# nfc_lock.net
KiCad netlist of a schematic drawn in EAGLE
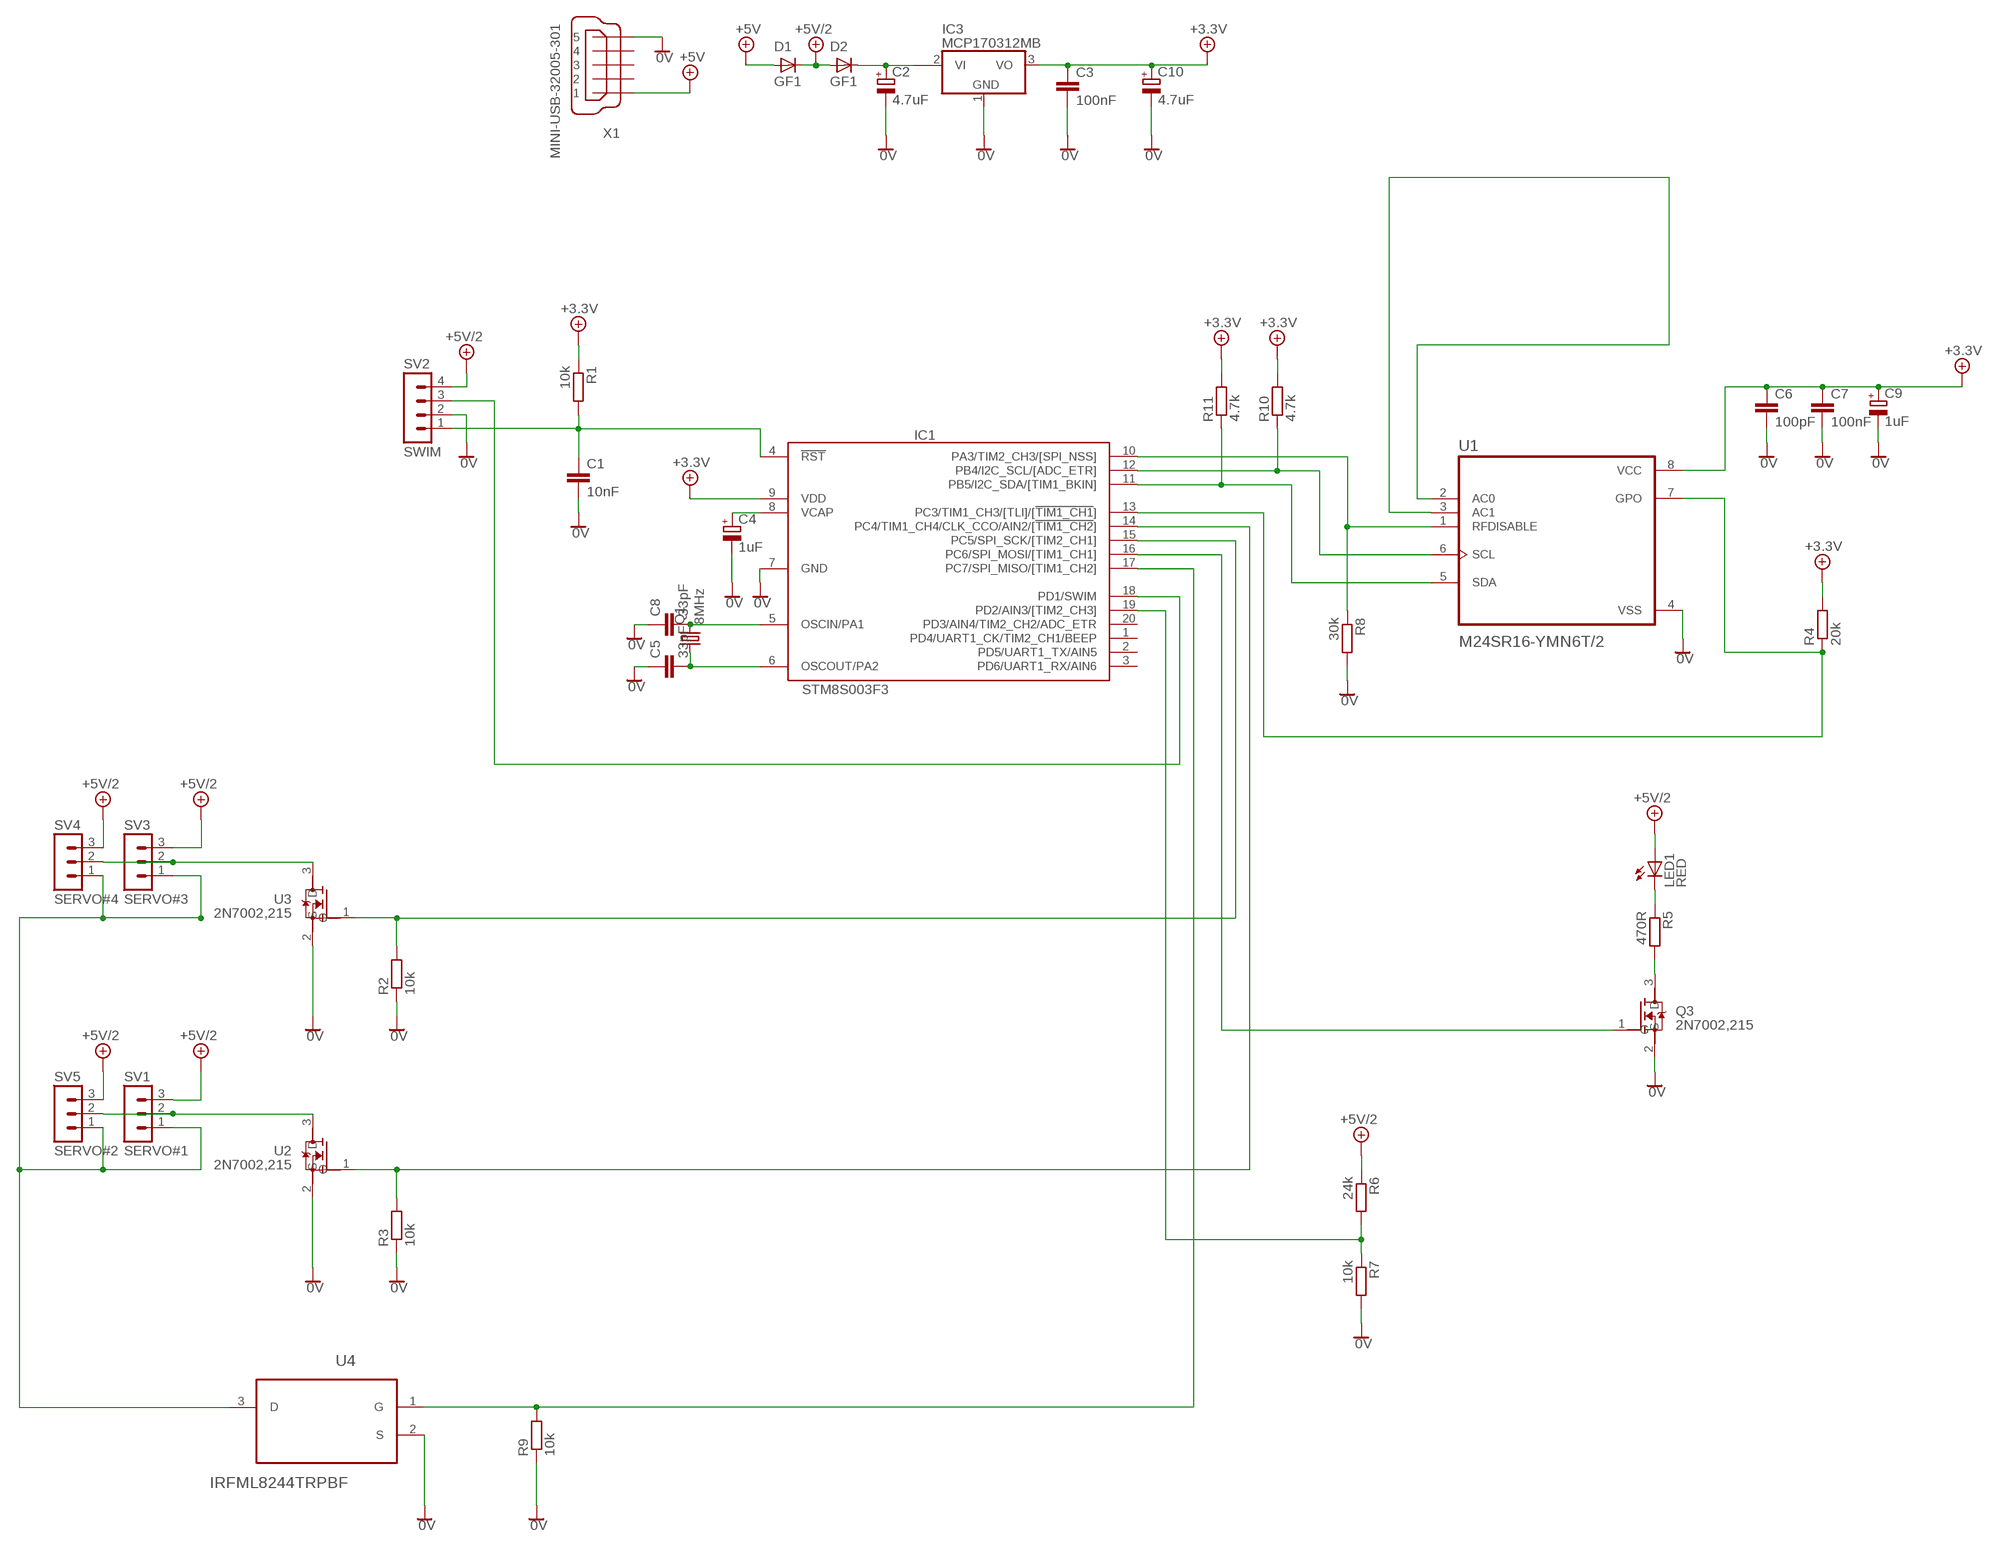
[diagram p0: schematic, sheet 1]

(export (version "E")
  (design (tool "Eeschema 10.0.6"))
  (components
    (comp (ref "C1")
      (value "10nF")
      (footprint "eagle-import:C0603K")
      (libsource (lib "eagle-import") (part "C-EUC0603K"))
    )
    (comp (ref "C2")
      (value "4.7uF")
      (footprint "eagle-import:153CLV-0405")
      (libsource (lib "eagle-import") (part "CPOL-EU153CLV-0405"))
    )
    (comp (ref "C3")
      (value "100nF")
      (footprint "eagle-import:C1206")
      (libsource (lib "eagle-import") (part "C-EUC1206"))
    )
    (comp (ref "C4")
      (value "1uF")
      (footprint "eagle-import:153CLV-0405")
      (libsource (lib "eagle-import") (part "CPOL-EU153CLV-0405"))
    )
    (comp (ref "C5")
      (value "33pF")
      (footprint "eagle-import:C0603K")
      (libsource (lib "eagle-import") (part "C-EUC0603K"))
    )
    (comp (ref "C6")
      (value "100pF")
      (footprint "eagle-import:C1206")
      (libsource (lib "eagle-import") (part "C-EUC1206"))
    )
    (comp (ref "C7")
      (value "100nF")
      (footprint "eagle-import:C1206")
      (libsource (lib "eagle-import") (part "C-EUC1206"))
    )
    (comp (ref "C8")
      (value "33pF")
      (footprint "eagle-import:C0603K")
      (libsource (lib "eagle-import") (part "C-EUC0603K"))
    )
    (comp (ref "C9")
      (value "1uF")
      (footprint "eagle-import:153CLV-0405")
      (libsource (lib "eagle-import") (part "CPOL-EU153CLV-0405"))
    )
    (comp (ref "C10")
      (value "4.7uF")
      (footprint "eagle-import:153CLV-0405")
      (libsource (lib "eagle-import") (part "CPOL-EU153CLV-0405"))
    )
    (comp (ref "D1")
      (value "GF1")
      (footprint "eagle-import:SMA-DO214AC")
      (libsource (lib "eagle-import") (part "GF1"))
    )
    (comp (ref "D2")
      (value "GF1")
      (footprint "eagle-import:SMA-DO214AC")
      (libsource (lib "eagle-import") (part "GF1"))
    )
    (comp (ref "IC1")
      (value "STM8S003F3")
      (footprint "eagle-import:TSSOP20")
      (libsource (lib "eagle-import") (part "STM8S003F3"))
    )
    (comp (ref "IC3")
      (value "MCP170312MB")
      (footprint "eagle-import:SOT89")
      (libsource (lib "eagle-import") (part "MCP1703MB12"))
    )
    (comp (ref "LED1")
      (value "RED")
      (footprint "eagle-import:CHIP-LED0603")
      (libsource (lib "eagle-import") (part "LEDCHIP-LED0603"))
    )
    (comp (ref "Q1")
      (value "8MHz")
      (footprint "eagle-import:SM49")
      (libsource (lib "eagle-import") (part "CRYSTALSM49"))
    )
    (comp (ref "Q3")
      (value "2N7002,215")
      (footprint "eagle-import:SOT95P230X110-3N")
      (fields (field (name "MANUFACTURER") "NXP Semiconductor"))
      (libsource (lib "eagle-import") (part "2N7002,215"))
    )
    (comp (ref "R1")
      (value "10k")
      (footprint "eagle-import:R0805")
      (libsource (lib "eagle-import") (part "R-EU_R0805"))
    )
    (comp (ref "R2")
      (value "10k")
      (footprint "eagle-import:R0805")
      (libsource (lib "eagle-import") (part "R-EU_R0805"))
    )
    (comp (ref "R3")
      (value "10k")
      (footprint "eagle-import:R0805")
      (libsource (lib "eagle-import") (part "R-EU_R0805"))
    )
    (comp (ref "R4")
      (value "20k")
      (footprint "eagle-import:R0805")
      (libsource (lib "eagle-import") (part "R-EU_R0805"))
    )
    (comp (ref "R5")
      (value "470R")
      (footprint "eagle-import:R0805")
      (libsource (lib "eagle-import") (part "R-EU_R0805"))
    )
    (comp (ref "R6")
      (value "24k")
      (footprint "eagle-import:R0805")
      (libsource (lib "eagle-import") (part "R-EU_R0805"))
    )
    (comp (ref "R7")
      (value "10k")
      (footprint "eagle-import:R0805")
      (libsource (lib "eagle-import") (part "R-EU_R0805"))
    )
    (comp (ref "R8")
      (value "30k")
      (footprint "eagle-import:R0805")
      (libsource (lib "eagle-import") (part "R-EU_R0805"))
    )
    (comp (ref "R9")
      (value "10k")
      (footprint "eagle-import:R0805")
      (libsource (lib "eagle-import") (part "R-EU_R0805"))
    )
    (comp (ref "R10")
      (value "4.7k")
      (footprint "eagle-import:R0805")
      (libsource (lib "eagle-import") (part "R-EU_R0805"))
    )
    (comp (ref "R11")
      (value "4.7k")
      (footprint "eagle-import:R0805")
      (libsource (lib "eagle-import") (part "R-EU_R0805"))
    )
    (comp (ref "SV1")
      (value "SERVO#1")
      (footprint "eagle-import:MA03-1")
      (libsource (lib "eagle-import") (part "MA03-1"))
    )
    (comp (ref "SV2")
      (value "SWIM")
      (footprint "eagle-import:MA04-1")
      (libsource (lib "eagle-import") (part "MA04-1"))
    )
    (comp (ref "SV3")
      (value "SERVO#3")
      (footprint "eagle-import:MA03-1")
      (libsource (lib "eagle-import") (part "MA03-1"))
    )
    (comp (ref "SV4")
      (value "SERVO#4")
      (footprint "eagle-import:MA03-1")
      (libsource (lib "eagle-import") (part "MA03-1"))
    )
    (comp (ref "SV5")
      (value "SERVO#2")
      (footprint "eagle-import:MA03-1")
      (libsource (lib "eagle-import") (part "MA03-1"))
    )
    (comp (ref "U1")
      (value "M24SR16-YMN6T/2")
      (footprint "eagle-import:SOIC127P600X175-8N")
      (fields (field (name "MF") "STMicroelectronics"))
      (libsource (lib "eagle-import") (part "M24SR16-YMN6T/2"))
    )
    (comp (ref "U2")
      (value "2N7002,215")
      (footprint "eagle-import:SOT95P230X110-3N")
      (fields (field (name "MANUFACTURER") "NXP Semiconductor"))
      (libsource (lib "eagle-import") (part "2N7002,215"))
    )
    (comp (ref "U3")
      (value "2N7002,215")
      (footprint "eagle-import:SOT95P230X110-3N")
      (fields (field (name "MANUFACTURER") "NXP Semiconductor"))
      (libsource (lib "eagle-import") (part "2N7002,215"))
    )
    (comp (ref "U4")
      (value "IRFML8244TRPBF")
      (footprint "eagle-import:SOT95P240X112-3N")
      (libsource (lib "eagle-import") (part "IRFML8244TRPBF"))
    )
    (comp (ref "X1")
      (value "MINI-USB-32005-301")
      (footprint "eagle-import:32005-301")
      (libsource (lib "eagle-import") (part "MINI-USB-32005-301"))
    )
  )
  (nets
    (net (code "1") (name "+3.3V") (class "Default")
      (node (ref "C10") (pin "+") (pinfunction "+_+") (pintype "passive"))
      (node (ref "C3") (pin "1") (pinfunction "1_1") (pintype "passive"))
      (node (ref "C6") (pin "1") (pinfunction "1_1") (pintype "passive"))
      (node (ref "C7") (pin "1") (pinfunction "1_1") (pintype "passive"))
      (node (ref "C9") (pin "+") (pinfunction "+_+") (pintype "passive"))
      (node (ref "IC1") (pin "9") (pinfunction "VDD_9") (pintype "power_in"))
      (node (ref "IC3") (pin "3") (pinfunction "VO_3") (pintype "passive"))
      (node (ref "R1") (pin "1") (pinfunction "1_1") (pintype "passive"))
      (node (ref "R10") (pin "2") (pinfunction "2_2") (pintype "passive"))
      (node (ref "R11") (pin "2") (pinfunction "2_2") (pintype "passive"))
      (node (ref "R4") (pin "2") (pinfunction "2_2") (pintype "passive"))
      (node (ref "U1") (pin "8") (pinfunction "VCC_8") (pintype "power_in"))
    )
    (net (code "2") (name "+5V") (class "Default")
      (node (ref "D1") (pin "A") (pinfunction "A_A") (pintype "passive"))
      (node (ref "X1") (pin "1") (pinfunction "1_1") (pintype "passive"))
    )
    (net (code "3") (name "+5V{slash}2") (class "Default")
      (node (ref "D1") (pin "K") (pinfunction "C_K") (pintype "passive"))
      (node (ref "D2") (pin "A") (pinfunction "A_A") (pintype "passive"))
      (node (ref "LED1") (pin "A") (pinfunction "A_A") (pintype "passive"))
      (node (ref "R6") (pin "1") (pinfunction "1_1") (pintype "passive"))
      (node (ref "SV1") (pin "3") (pinfunction "3_3") (pintype "passive"))
      (node (ref "SV2") (pin "4") (pinfunction "4_4") (pintype "passive"))
      (node (ref "SV3") (pin "3") (pinfunction "3_3") (pintype "passive"))
      (node (ref "SV4") (pin "3") (pinfunction "3_3") (pintype "passive"))
      (node (ref "SV5") (pin "3") (pinfunction "3_3") (pintype "passive"))
    )
    (net (code "4") (name "0V") (class "Default")
      (node (ref "C1") (pin "2") (pinfunction "2_2") (pintype "passive"))
      (node (ref "C10") (pin "-") (pinfunction "-_-") (pintype "passive"))
      (node (ref "C2") (pin "-") (pinfunction "-_-") (pintype "passive"))
      (node (ref "C3") (pin "2") (pinfunction "2_2") (pintype "passive"))
      (node (ref "C4") (pin "-") (pinfunction "-_-") (pintype "passive"))
      (node (ref "C5") (pin "1") (pinfunction "1_1") (pintype "passive"))
      (node (ref "C6") (pin "2") (pinfunction "2_2") (pintype "passive"))
      (node (ref "C7") (pin "2") (pinfunction "2_2") (pintype "passive"))
      (node (ref "C8") (pin "1") (pinfunction "1_1") (pintype "passive"))
      (node (ref "C9") (pin "-") (pinfunction "-_-") (pintype "passive"))
      (node (ref "IC1") (pin "7") (pinfunction "GND_7") (pintype "power_in"))
      (node (ref "IC3") (pin "1") (pinfunction "GND_1") (pintype "passive"))
      (node (ref "Q3") (pin "2") (pinfunction "S_2") (pintype "passive"))
      (node (ref "R2") (pin "1") (pinfunction "1_1") (pintype "passive"))
      (node (ref "R3") (pin "1") (pinfunction "1_1") (pintype "passive"))
      (node (ref "R7") (pin "2") (pinfunction "2_2") (pintype "passive"))
      (node (ref "R8") (pin "2") (pinfunction "2_2") (pintype "passive"))
      (node (ref "R9") (pin "1") (pinfunction "1_1") (pintype "passive"))
      (node (ref "SV2") (pin "2") (pinfunction "2_2") (pintype "passive"))
      (node (ref "U1") (pin "4") (pinfunction "VSS_4") (pintype "power_in"))
      (node (ref "U2") (pin "2") (pinfunction "S_2") (pintype "passive"))
      (node (ref "U3") (pin "2") (pinfunction "S_2") (pintype "passive"))
      (node (ref "U4") (pin "2") (pinfunction "S_2") (pintype "passive"))
      (node (ref "X1") (pin "5") (pinfunction "5_5") (pintype "passive"))
    )
    (net (code "5") (name "Net-(D2-C)") (class "Default")
      (node (ref "C2") (pin "+") (pinfunction "+_+") (pintype "passive"))
      (node (ref "D2") (pin "K") (pinfunction "C_K") (pintype "passive"))
      (node (ref "IC3") (pin "2@1") (pinfunction "VI1_2@1") (pintype "input"))
    )
    (net (code "6") (name "Net-(IC1-OSCIN{slash}PA1)") (class "Default")
      (node (ref "C8") (pin "2") (pinfunction "2_2") (pintype "passive"))
      (node (ref "IC1") (pin "5") (pinfunction "OSCIN/PA1_5") (pintype "bidirectional"))
      (node (ref "Q1") (pin "2") (pinfunction "2_2") (pintype "passive"))
    )
    (net (code "7") (name "Net-(IC1-OSCOUT{slash}PA2)") (class "Default")
      (node (ref "C5") (pin "2") (pinfunction "2_2") (pintype "passive"))
      (node (ref "IC1") (pin "6") (pinfunction "OSCOUT/PA2_6") (pintype "bidirectional"))
      (node (ref "Q1") (pin "1") (pinfunction "1_1") (pintype "passive"))
    )
    (net (code "8") (name "Net-(IC1-PA3{slash}TIM2_CH3{slash}[SPI_NSS])") (class "Default")
      (node (ref "IC1") (pin "10") (pinfunction "PA3/TIM2_CH3/[SPI_NSS]_10") (pintype "bidirectional"))
      (node (ref "R8") (pin "1") (pinfunction "1_1") (pintype "passive"))
      (node (ref "U1") (pin "1") (pinfunction "RFDISABLE_1") (pintype "input"))
    )
    (net (code "9") (name "Net-(IC1-PB4{slash}I2C_SCL{slash}[ADC_ETR])") (class "Default")
      (node (ref "IC1") (pin "12") (pinfunction "PB4/I2C_SCL/[ADC_ETR]_12") (pintype "bidirectional"))
      (node (ref "R10") (pin "1") (pinfunction "1_1") (pintype "passive"))
      (node (ref "U1") (pin "6") (pinfunction "SCL_6") (pintype "input"))
    )
    (net (code "10") (name "Net-(IC1-PB5{slash}I2C_SDA{slash}[TIM1_BKIN])") (class "Default")
      (node (ref "IC1") (pin "11") (pinfunction "PB5/I2C_SDA/[TIM1_BKIN]_11") (pintype "bidirectional"))
      (node (ref "R11") (pin "1") (pinfunction "1_1") (pintype "passive"))
      (node (ref "U1") (pin "5") (pinfunction "SDA_5") (pintype "bidirectional"))
    )
    (net (code "11") (name "Net-(IC1-PC3{slash}TIM1_CH3{slash}[TLI]{slash}[~{TIM1_CH1}])") (class "Default")
      (node (ref "IC1") (pin "13") (pinfunction "PC3/TIM1_CH3/[TLI]/[~{TIM1_CH1}]_13") (pintype "bidirectional"))
      (node (ref "R4") (pin "1") (pinfunction "1_1") (pintype "passive"))
      (node (ref "U1") (pin "7") (pinfunction "GPO_7") (pintype "output"))
    )
    (net (code "12") (name "Net-(IC1-PC4{slash}TIM1_CH4{slash}CLK_CCO{slash}AIN2{slash}[~{TIM1_CH2}])") (class "Default")
      (node (ref "IC1") (pin "14") (pinfunction "PC4/TIM1_CH4/CLK_CCO/AIN2/[~{TIM1_CH2}]_14") (pintype "bidirectional"))
      (node (ref "R3") (pin "2") (pinfunction "2_2") (pintype "passive"))
      (node (ref "U2") (pin "1") (pinfunction "G_1") (pintype "passive"))
    )
    (net (code "13") (name "Net-(IC1-PC5{slash}SPI_SCK{slash}[TIM2_CH1])") (class "Default")
      (node (ref "IC1") (pin "15") (pinfunction "PC5/SPI_SCK/[TIM2_CH1]_15") (pintype "bidirectional"))
      (node (ref "R2") (pin "2") (pinfunction "2_2") (pintype "passive"))
      (node (ref "U3") (pin "1") (pinfunction "G_1") (pintype "passive"))
    )
    (net (code "14") (name "Net-(IC1-PC6{slash}SPI_MOSI{slash}[TIM1_CH1])") (class "Default")
      (node (ref "IC1") (pin "16") (pinfunction "PC6/SPI_MOSI/[TIM1_CH1]_16") (pintype "bidirectional"))
      (node (ref "Q3") (pin "1") (pinfunction "G_1") (pintype "passive"))
    )
    (net (code "15") (name "Net-(IC1-PC7{slash}SPI_MISO{slash}[TIM1_CH2])") (class "Default")
      (node (ref "IC1") (pin "17") (pinfunction "PC7/SPI_MISO/[TIM1_CH2]_17") (pintype "bidirectional"))
      (node (ref "R9") (pin "2") (pinfunction "2_2") (pintype "passive"))
      (node (ref "U4") (pin "1") (pinfunction "G_1") (pintype "input"))
    )
    (net (code "16") (name "Net-(IC1-PD1{slash}SWIM)") (class "Default")
      (node (ref "IC1") (pin "18") (pinfunction "PD1/SWIM_18") (pintype "bidirectional"))
      (node (ref "SV2") (pin "3") (pinfunction "3_3") (pintype "passive"))
    )
    (net (code "17") (name "Net-(IC1-PD2{slash}AIN3{slash}[TIM2_CH3])") (class "Default")
      (node (ref "IC1") (pin "19") (pinfunction "PD2/AIN3/[TIM2_CH3]_19") (pintype "bidirectional"))
      (node (ref "R6") (pin "2") (pinfunction "2_2") (pintype "passive"))
      (node (ref "R7") (pin "1") (pinfunction "1_1") (pintype "passive"))
    )
    (net (code "18") (name "Net-(IC1-VCAP)") (class "Default")
      (node (ref "C4") (pin "+") (pinfunction "+_+") (pintype "passive"))
      (node (ref "IC1") (pin "8") (pinfunction "VCAP_8") (pintype "power_in"))
    )
    (net (code "19") (name "Net-(IC1-~{RST})") (class "Default")
      (node (ref "C1") (pin "1") (pinfunction "1_1") (pintype "passive"))
      (node (ref "IC1") (pin "4") (pinfunction "~{RST}_4") (pintype "input"))
      (node (ref "R1") (pin "2") (pinfunction "2_2") (pintype "passive"))
      (node (ref "SV2") (pin "1") (pinfunction "1_1") (pintype "passive"))
    )
    (net (code "20") (name "Net-(LED1-PadC)") (class "Default")
      (node (ref "LED1") (pin "C") (pinfunction "C_C") (pintype "passive"))
      (node (ref "R5") (pin "1") (pinfunction "1_1") (pintype "passive"))
    )
    (net (code "21") (name "Net-(Q3-D)") (class "Default")
      (node (ref "Q3") (pin "3") (pinfunction "D_3") (pintype "passive"))
      (node (ref "R5") (pin "2") (pinfunction "2_2") (pintype "passive"))
    )
    (net (code "22") (name "Net-(U1-AC0)") (class "Default")
      (node (ref "U1") (pin "2") (pinfunction "AC0_2") (pintype "input"))
      (node (ref "U1") (pin "3") (pinfunction "AC1_3") (pintype "input"))
    )
    (net (code "23") (name "Net-(U2-D)") (class "Default")
      (node (ref "SV1") (pin "2") (pinfunction "2_2") (pintype "passive"))
      (node (ref "SV5") (pin "2") (pinfunction "2_2") (pintype "passive"))
      (node (ref "U2") (pin "3") (pinfunction "D_3") (pintype "passive"))
    )
    (net (code "24") (name "Net-(U3-D)") (class "Default")
      (node (ref "SV3") (pin "2") (pinfunction "2_2") (pintype "passive"))
      (node (ref "SV4") (pin "2") (pinfunction "2_2") (pintype "passive"))
      (node (ref "U3") (pin "3") (pinfunction "D_3") (pintype "passive"))
    )
    (net (code "25") (name "Net-(U4-D)") (class "Default")
      (node (ref "SV1") (pin "1") (pinfunction "1_1") (pintype "passive"))
      (node (ref "SV3") (pin "1") (pinfunction "1_1") (pintype "passive"))
      (node (ref "SV4") (pin "1") (pinfunction "1_1") (pintype "passive"))
      (node (ref "SV5") (pin "1") (pinfunction "1_1") (pintype "passive"))
      (node (ref "U4") (pin "3") (pinfunction "D_3") (pintype "output"))
    )
    (net (code "26") (name "unconnected-(IC1-PD3{slash}AIN4{slash}TIM2_CH2{slash}ADC_ETR-Pad20)") (class "Default")
      (node (ref "IC1") (pin "20") (pinfunction "PD3/AIN4/TIM2_CH2/ADC_ETR_20") (pintype "bidirectional"))
    )
    (net (code "27") (name "unconnected-(IC1-PD4{slash}UART1_CK{slash}TIM2_CH1{slash}BEEP-Pad1)") (class "Default")
      (node (ref "IC1") (pin "1") (pinfunction "PD4/UART1_CK/TIM2_CH1/BEEP_1") (pintype "bidirectional"))
    )
    (net (code "28") (name "unconnected-(IC1-PD5{slash}UART1_TX{slash}AIN5-Pad2)") (class "Default")
      (node (ref "IC1") (pin "2") (pinfunction "PD5/UART1_TX/AIN5_2") (pintype "bidirectional"))
    )
    (net (code "29") (name "unconnected-(IC1-PD6{slash}UART1_RX{slash}AIN6-Pad3)") (class "Default")
      (node (ref "IC1") (pin "3") (pinfunction "PD6/UART1_RX/AIN6_3") (pintype "bidirectional"))
    )
    (net (code "30") (name "unconnected-(IC3-VI-Pad2)") (class "Default")
      (node (ref "IC3") (pin "2") (pinfunction "VI_2") (pintype "input"))
    )
    (net (code "31") (name "unconnected-(X1-Pad2)") (class "Default")
      (node (ref "X1") (pin "2") (pinfunction "2_2") (pintype "passive"))
    )
    (net (code "32") (name "unconnected-(X1-Pad3)") (class "Default")
      (node (ref "X1") (pin "3") (pinfunction "3_3") (pintype "passive"))
    )
    (net (code "33") (name "unconnected-(X1-Pad4)") (class "Default")
      (node (ref "X1") (pin "4") (pinfunction "4_4") (pintype "passive"))
    )
  )
)
